# Ethernet_Shield.net
KiCad netlist of a schematic drawn in EAGLE
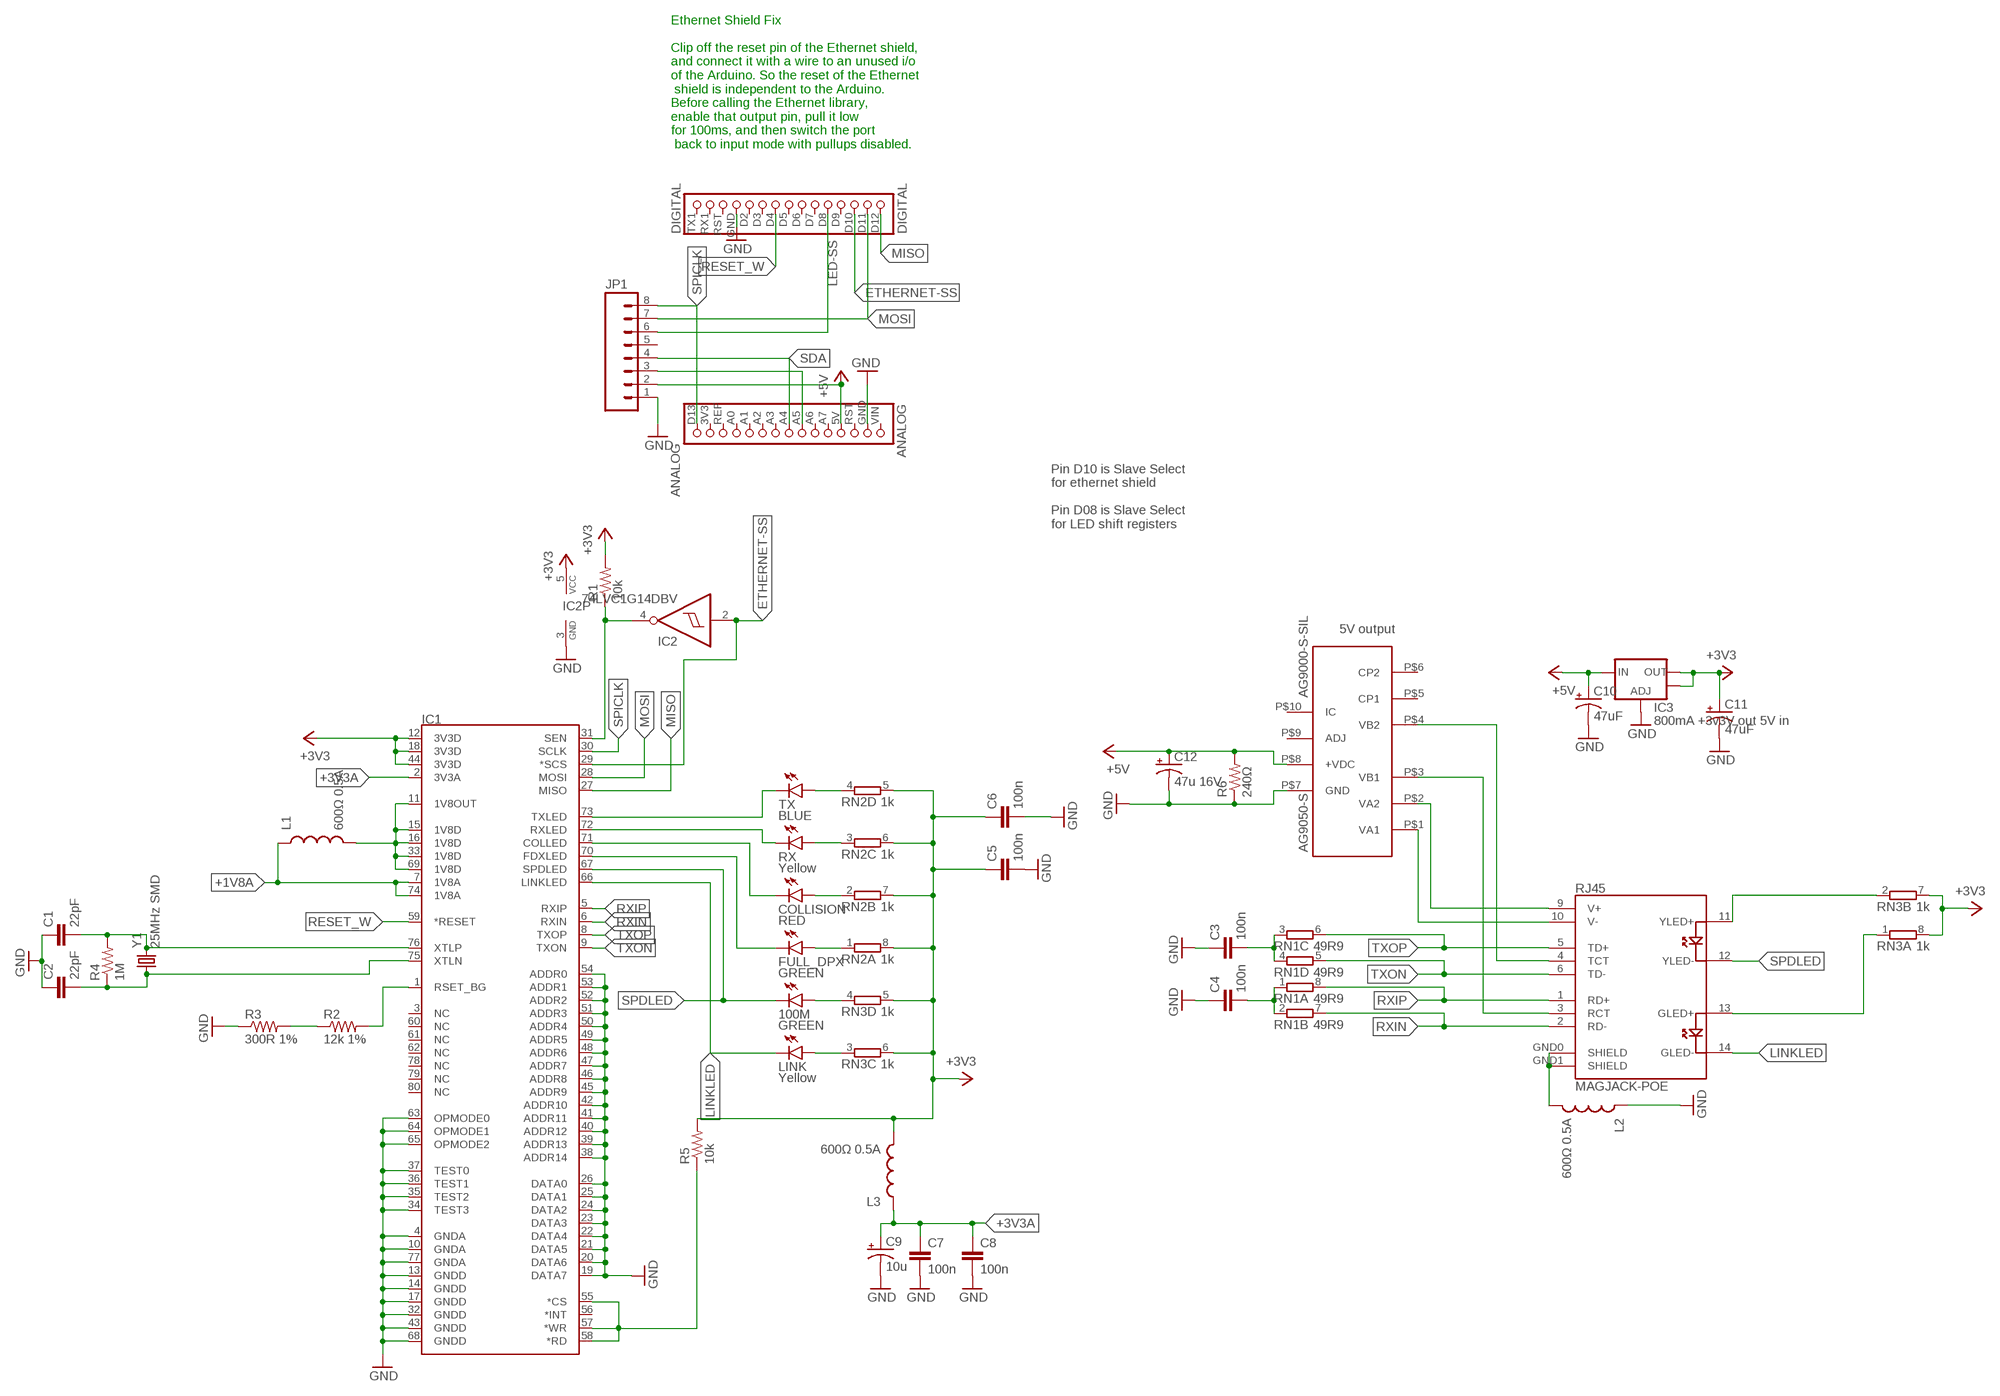
[diagram p0: schematic, sheet 1]

(export (version "E")
  (design (tool "Eeschema 10.0.6"))
  (components
    (comp (ref "100M")
      (value "GREEN")
      (footprint "eagle-import:LED-0603")
      (libsource (lib "eagle-import") (part "LED-GREEN0603"))
    )
    (comp (ref "AG9050-S")
      (value "AG9000-S-SIL")
      (footprint "eagle-import:AG9000-S")
      (libsource (lib "eagle-import") (part "AG9000-S-SIL"))
    )
    (comp (ref "ANALOG")
      (value "ANALOG")
      (footprint "eagle-import:A1X15")
      (libsource (lib "eagle-import") (part "ANALOG"))
    )
    (comp (ref "C1")
      (value "22pF")
      (footprint "eagle-import:0603-CAP")
      (libsource (lib "eagle-import") (part "22PF-50V-5%(0603)"))
    )
    (comp (ref "C2")
      (value "22pF")
      (footprint "eagle-import:0603-CAP")
      (libsource (lib "eagle-import") (part "22PF-50V-5%(0603)"))
    )
    (comp (ref "C3")
      (value "100n")
      (footprint "eagle-import:0402-CAP")
      (libsource (lib "eagle-import") (part "CAP0402-CAP"))
    )
    (comp (ref "C4")
      (value "100n")
      (footprint "eagle-import:0402-CAP")
      (libsource (lib "eagle-import") (part "CAP0402-CAP"))
    )
    (comp (ref "C5")
      (value "100n")
      (footprint "eagle-import:0402-CAP")
      (libsource (lib "eagle-import") (part "CAP0402-CAP"))
    )
    (comp (ref "C6")
      (value "100n")
      (footprint "eagle-import:0402-CAP")
      (libsource (lib "eagle-import") (part "CAP0402-CAP"))
    )
    (comp (ref "C7")
      (value "100n")
      (footprint "eagle-import:0402-CAP")
      (libsource (lib "eagle-import") (part "CAP0402-CAP"))
    )
    (comp (ref "C8")
      (value "100n")
      (footprint "eagle-import:0402-CAP")
      (libsource (lib "eagle-import") (part "CAP0402-CAP"))
    )
    (comp (ref "C9")
      (value "10u")
      (footprint "eagle-import:EIA3216")
      (libsource (lib "eagle-import") (part "CAP_POL1206"))
    )
    (comp (ref "C10")
      (value "47uF")
      (footprint "eagle-import:EIA3528")
      (libsource (lib "eagle-import") (part "47UF-10V-10%(TANT)"))
    )
    (comp (ref "C11")
      (value "47uF")
      (footprint "eagle-import:EIA3528")
      (libsource (lib "eagle-import") (part "47UF-10V-10%(TANT)"))
    )
    (comp (ref "C12")
      (value "47u 16V")
      (footprint "eagle-import:EIA3216")
      (libsource (lib "eagle-import") (part "CAP_POL1206"))
    )
    (comp (ref "COLLISION")
      (value "RED")
      (footprint "eagle-import:LED-0603")
      (libsource (lib "eagle-import") (part "LED-RED0603"))
    )
    (comp (ref "DIGITAL")
      (value "DIGITAL")
      (footprint "eagle-import:1X15")
      (libsource (lib "eagle-import") (part "DIGITALDIGITAL''"))
    )
    (comp (ref "FULL_DPX")
      (value "GREEN")
      (footprint "eagle-import:LED-0603")
      (libsource (lib "eagle-import") (part "LED-GREEN0603"))
    )
    (comp (ref "IC1")
      (value "W5100")
      (footprint "eagle-import:LQFP-80")
      (libsource (lib "eagle-import") (part "W5100"))
    )
    (comp (ref "IC2")
      (value "74LVC1G14DBV")
      (footprint "eagle-import:SOT23-5")
      (libsource (lib "eagle-import") (part "741G14DBVLVC"))
    )
    (comp (ref "IC3")
      (value "800mA +3v3V out 5V in")
      (footprint "eagle-import:SOT223")
      (libsource (lib "eagle-import") (part "V_REG_LM1117SOT223"))
    )
    (comp (ref "JP1")
      (value "M08")
      (footprint "eagle-import:1X08_ROUND")
      (libsource (lib "eagle-import") (part "M08"))
    )
    (comp (ref "L1")
      (value "600Ω 0.5A")
      (footprint "eagle-import:0805")
      (libsource (lib "eagle-import") (part "INDUCTOR0805"))
    )
    (comp (ref "L2")
      (value "600Ω 0.5A")
      (footprint "eagle-import:0805")
      (libsource (lib "eagle-import") (part "INDUCTOR0805"))
    )
    (comp (ref "L3")
      (value "600Ω 0.5A")
      (footprint "eagle-import:0805")
      (libsource (lib "eagle-import") (part "INDUCTOR0805"))
    )
    (comp (ref "LINK")
      (value "Yellow")
      (footprint "eagle-import:LED-0603")
      (libsource (lib "eagle-import") (part "LED-YELLOW0603"))
    )
    (comp (ref "R1")
      (value "10k")
      (footprint "eagle-import:0402-RES")
      (libsource (lib "eagle-import") (part "RESISTOR0402-RES"))
    )
    (comp (ref "R2")
      (value "12k 1%")
      (footprint "eagle-import:0402-RES")
      (libsource (lib "eagle-import") (part "RESISTOR0402-RES"))
    )
    (comp (ref "R3")
      (value "300R 1%")
      (footprint "eagle-import:0402-RES")
      (libsource (lib "eagle-import") (part "RESISTOR0402-RES"))
    )
    (comp (ref "R4")
      (value "1M")
      (footprint "eagle-import:0402-RES")
      (libsource (lib "eagle-import") (part "RESISTOR0402-RES"))
    )
    (comp (ref "R5")
      (value "10k")
      (footprint "eagle-import:0402-RES")
      (libsource (lib "eagle-import") (part "RESISTOR0402-RES"))
    )
    (comp (ref "R6")
      (value "240Ω")
      (footprint "eagle-import:0402-RES")
      (libsource (lib "eagle-import") (part "RESISTOR0402-RES"))
    )
    (comp (ref "RJ45")
      (value "MAGJACK-POE")
      (footprint "eagle-import:MAGJACK-POE")
      (libsource (lib "eagle-import") (part "MAGJACK-POE"))
    )
    (comp (ref "RN1")
      (value "49R9")
      (footprint "eagle-import:CAY16")
      (libsource (lib "eagle-import") (part "4R-NCAY16"))
    )
    (comp (ref "RN2")
      (value "1k")
      (footprint "eagle-import:CAY16")
      (libsource (lib "eagle-import") (part "4R-NCAY16"))
    )
    (comp (ref "RN3")
      (value "1k")
      (footprint "eagle-import:CAY16")
      (libsource (lib "eagle-import") (part "4R-NCAY16"))
    )
    (comp (ref "RX")
      (value "Yellow")
      (footprint "eagle-import:LED-0603")
      (libsource (lib "eagle-import") (part "LED-YELLOW0603"))
    )
    (comp (ref "TX")
      (value "BLUE")
      (footprint "eagle-import:LED-0603")
      (libsource (lib "eagle-import") (part "LED-BLUE0603"))
    )
    (comp (ref "Y1")
      (value "25MHz SMD")
      (footprint "eagle-import:HC49UP")
      (libsource (lib "eagle-import") (part "CRYSTALSMD"))
    )
  )
  (nets
    (net (code "1") (name "+1V8A") (class "Default")
      (node (ref "IC1") (pin "7") (pinfunction "1V8A_7") (pintype "bidirectional"))
      (node (ref "IC1") (pin "74") (pinfunction "1V8A_74") (pintype "bidirectional"))
      (node (ref "L1") (pin "1") (pinfunction "1_1") (pintype "passive"))
    )
    (net (code "2") (name "+3V3") (class "Default")
      (node (ref "C11") (pin "A") (pinfunction "+_A") (pintype "passive"))
      (node (ref "C5") (pin "1") (pinfunction "1_1") (pintype "passive"))
      (node (ref "C6") (pin "1") (pinfunction "1_1") (pintype "passive"))
      (node (ref "IC1") (pin "12") (pinfunction "3V3D_12") (pintype "bidirectional"))
      (node (ref "IC1") (pin "18") (pinfunction "3V3D_18") (pintype "bidirectional"))
      (node (ref "IC1") (pin "44") (pinfunction "3V3D_44") (pintype "bidirectional"))
      (node (ref "IC2") (pin "5") (pinfunction "VCC_5") (pintype "power_in"))
      (node (ref "IC3") (pin "2") (pinfunction "OUT_2") (pintype "output"))
      (node (ref "IC3") (pin "4") (pinfunction "OUT_4") (pintype "output"))
      (node (ref "L3") (pin "2") (pinfunction "2_2") (pintype "passive"))
      (node (ref "R1") (pin "2") (pinfunction "2_2") (pintype "passive"))
      (node (ref "R5") (pin "2") (pinfunction "2_2") (pintype "passive"))
      (node (ref "RN2") (pin "5") (pinfunction "2_5") (pintype "passive"))
      (node (ref "RN2") (pin "6") (pinfunction "2_6") (pintype "passive"))
      (node (ref "RN2") (pin "7") (pinfunction "2_7") (pintype "passive"))
      (node (ref "RN2") (pin "8") (pinfunction "2_8") (pintype "passive"))
      (node (ref "RN3") (pin "5") (pinfunction "2_5") (pintype "passive"))
      (node (ref "RN3") (pin "6") (pinfunction "2_6") (pintype "passive"))
      (node (ref "RN3") (pin "7") (pinfunction "2_7") (pintype "passive"))
      (node (ref "RN3") (pin "8") (pinfunction "2_8") (pintype "passive"))
    )
    (net (code "3") (name "+3V3A") (class "Default")
      (node (ref "C7") (pin "1") (pinfunction "1_1") (pintype "passive"))
      (node (ref "C8") (pin "1") (pinfunction "1_1") (pintype "passive"))
      (node (ref "C9") (pin "A") (pinfunction "+_A") (pintype "passive"))
      (node (ref "IC1") (pin "2") (pinfunction "3V3A_2") (pintype "bidirectional"))
      (node (ref "L3") (pin "1") (pinfunction "1_1") (pintype "passive"))
    )
    (net (code "4") (name "+5V") (class "Default")
      (node (ref "AG9050-S") (pin "P$8") (pinfunction "+VDC_P$8") (pintype "output"))
      (node (ref "ANALOG") (pin "5V") (pinfunction "5V_5V") (pintype "passive"))
      (node (ref "C10") (pin "A") (pinfunction "+_A") (pintype "passive"))
      (node (ref "C12") (pin "A") (pinfunction "+_A") (pintype "passive"))
      (node (ref "IC3") (pin "3") (pinfunction "IN_3") (pintype "input"))
      (node (ref "JP1") (pin "2") (pinfunction "2_2") (pintype "passive"))
      (node (ref "R6") (pin "2") (pinfunction "2_2") (pintype "passive"))
    )
    (net (code "5") (name "/LED-SS") (class "Default")
      (node (ref "DIGITAL") (pin "D8") (pinfunction "D8_D8") (pintype "passive"))
      (node (ref "JP1") (pin "6") (pinfunction "6_6") (pintype "passive"))
    )
    (net (code "6") (name "ETHERNET-SS") (class "Default")
      (node (ref "DIGITAL") (pin "D10") (pinfunction "D10_D10") (pintype "passive"))
      (node (ref "IC1") (pin "29") (pinfunction "*SCS_29") (pintype "bidirectional"))
      (node (ref "IC2") (pin "2") (pinfunction "I_2") (pintype "input"))
    )
    (net (code "7") (name "GND") (class "Default")
      (node (ref "AG9050-S") (pin "P$7") (pinfunction "GND_P$7") (pintype "bidirectional"))
      (node (ref "ANALOG") (pin "GND") (pinfunction "GND_GND") (pintype "passive"))
      (node (ref "C1") (pin "1") (pinfunction "1_1") (pintype "passive"))
      (node (ref "C10") (pin "C") (pinfunction "-_C") (pintype "passive"))
      (node (ref "C11") (pin "C") (pinfunction "-_C") (pintype "passive"))
      (node (ref "C12") (pin "C") (pinfunction "-_C") (pintype "passive"))
      (node (ref "C2") (pin "1") (pinfunction "1_1") (pintype "passive"))
      (node (ref "C3") (pin "1") (pinfunction "1_1") (pintype "passive"))
      (node (ref "C4") (pin "1") (pinfunction "1_1") (pintype "passive"))
      (node (ref "C5") (pin "2") (pinfunction "2_2") (pintype "passive"))
      (node (ref "C6") (pin "2") (pinfunction "2_2") (pintype "passive"))
      (node (ref "C7") (pin "2") (pinfunction "2_2") (pintype "passive"))
      (node (ref "C8") (pin "2") (pinfunction "2_2") (pintype "passive"))
      (node (ref "C9") (pin "C") (pinfunction "-_C") (pintype "passive"))
      (node (ref "DIGITAL") (pin "GND") (pinfunction "GND_GND") (pintype "passive"))
      (node (ref "IC1") (pin "10") (pinfunction "GNDA_10") (pintype "bidirectional"))
      (node (ref "IC1") (pin "13") (pinfunction "GNDD_13") (pintype "bidirectional"))
      (node (ref "IC1") (pin "14") (pinfunction "GNDD_14") (pintype "bidirectional"))
      (node (ref "IC1") (pin "17") (pinfunction "GNDD_17") (pintype "bidirectional"))
      (node (ref "IC1") (pin "19") (pinfunction "DATA7_19") (pintype "bidirectional"))
      (node (ref "IC1") (pin "20") (pinfunction "DATA6_20") (pintype "bidirectional"))
      (node (ref "IC1") (pin "21") (pinfunction "DATA5_21") (pintype "bidirectional"))
      (node (ref "IC1") (pin "22") (pinfunction "DATA4_22") (pintype "bidirectional"))
      (node (ref "IC1") (pin "23") (pinfunction "DATA3_23") (pintype "bidirectional"))
      (node (ref "IC1") (pin "24") (pinfunction "DATA2_24") (pintype "bidirectional"))
      (node (ref "IC1") (pin "25") (pinfunction "DATA1_25") (pintype "bidirectional"))
      (node (ref "IC1") (pin "26") (pinfunction "DATA0_26") (pintype "bidirectional"))
      (node (ref "IC1") (pin "32") (pinfunction "GNDD_32") (pintype "bidirectional"))
      (node (ref "IC1") (pin "34") (pinfunction "TEST3_34") (pintype "bidirectional"))
      (node (ref "IC1") (pin "35") (pinfunction "TEST2_35") (pintype "bidirectional"))
      (node (ref "IC1") (pin "36") (pinfunction "TEST1_36") (pintype "bidirectional"))
      (node (ref "IC1") (pin "37") (pinfunction "TEST0_37") (pintype "bidirectional"))
      (node (ref "IC1") (pin "38") (pinfunction "ADDR14_38") (pintype "bidirectional"))
      (node (ref "IC1") (pin "39") (pinfunction "ADDR13_39") (pintype "bidirectional"))
      (node (ref "IC1") (pin "4") (pinfunction "GNDA_4") (pintype "bidirectional"))
      (node (ref "IC1") (pin "40") (pinfunction "ADDR12_40") (pintype "bidirectional"))
      (node (ref "IC1") (pin "41") (pinfunction "ADDR11_41") (pintype "bidirectional"))
      (node (ref "IC1") (pin "42") (pinfunction "ADDR10_42") (pintype "bidirectional"))
      (node (ref "IC1") (pin "43") (pinfunction "GNDD_43") (pintype "bidirectional"))
      (node (ref "IC1") (pin "45") (pinfunction "ADDR9_45") (pintype "bidirectional"))
      (node (ref "IC1") (pin "46") (pinfunction "ADDR8_46") (pintype "bidirectional"))
      (node (ref "IC1") (pin "47") (pinfunction "ADDR7_47") (pintype "bidirectional"))
      (node (ref "IC1") (pin "48") (pinfunction "ADDR6_48") (pintype "bidirectional"))
      (node (ref "IC1") (pin "49") (pinfunction "ADDR5_49") (pintype "bidirectional"))
      (node (ref "IC1") (pin "50") (pinfunction "ADDR4_50") (pintype "bidirectional"))
      (node (ref "IC1") (pin "51") (pinfunction "ADDR3_51") (pintype "bidirectional"))
      (node (ref "IC1") (pin "52") (pinfunction "ADDR2_52") (pintype "bidirectional"))
      (node (ref "IC1") (pin "53") (pinfunction "ADDR1_53") (pintype "bidirectional"))
      (node (ref "IC1") (pin "54") (pinfunction "ADDR0_54") (pintype "bidirectional"))
      (node (ref "IC1") (pin "63") (pinfunction "OPMODE0_63") (pintype "bidirectional"))
      (node (ref "IC1") (pin "64") (pinfunction "OPMODE1_64") (pintype "bidirectional"))
      (node (ref "IC1") (pin "65") (pinfunction "OPMODE2_65") (pintype "bidirectional"))
      (node (ref "IC1") (pin "68") (pinfunction "GNDD_68") (pintype "bidirectional"))
      (node (ref "IC1") (pin "77") (pinfunction "GNDA_77") (pintype "bidirectional"))
      (node (ref "IC2") (pin "3") (pinfunction "GND_3") (pintype "power_in"))
      (node (ref "IC3") (pin "1") (pinfunction "ADJ_1") (pintype "input"))
      (node (ref "JP1") (pin "1") (pinfunction "1_1") (pintype "passive"))
      (node (ref "L2") (pin "1") (pinfunction "1_1") (pintype "passive"))
      (node (ref "R3") (pin "1") (pinfunction "1_1") (pintype "passive"))
      (node (ref "R6") (pin "1") (pinfunction "1_1") (pintype "passive"))
    )
    (net (code "8") (name "LINKLED") (class "Default")
      (node (ref "IC1") (pin "66") (pinfunction "LINKLED_66") (pintype "bidirectional"))
      (node (ref "LINK") (pin "C") (pinfunction "C_C") (pintype "passive"))
      (node (ref "RJ45") (pin "14") (pinfunction "GLED-_14") (pintype "bidirectional"))
    )
    (net (code "9") (name "MISO") (class "Default")
      (node (ref "DIGITAL") (pin "D12") (pinfunction "D12_D12") (pintype "passive"))
      (node (ref "IC1") (pin "27") (pinfunction "MISO_27") (pintype "bidirectional"))
    )
    (net (code "10") (name "MOSI") (class "Default")
      (node (ref "DIGITAL") (pin "D11") (pinfunction "D11_D11") (pintype "passive"))
      (node (ref "IC1") (pin "28") (pinfunction "MOSI_28") (pintype "bidirectional"))
      (node (ref "JP1") (pin "7") (pinfunction "7_7") (pintype "passive"))
    )
    (net (code "11") (name "Net-(AG9050-S-VA1)") (class "Default")
      (node (ref "AG9050-S") (pin "P$1") (pinfunction "VA1_P$1") (pintype "input"))
      (node (ref "RJ45") (pin "10") (pinfunction "V-_10") (pintype "bidirectional"))
    )
    (net (code "12") (name "Net-(AG9050-S-VA2)") (class "Default")
      (node (ref "AG9050-S") (pin "P$2") (pinfunction "VA2_P$2") (pintype "input"))
      (node (ref "RJ45") (pin "9") (pinfunction "V+_9") (pintype "bidirectional"))
    )
    (net (code "13") (name "Net-(AG9050-S-VB1)") (class "Default")
      (node (ref "AG9050-S") (pin "P$3") (pinfunction "VB1_P$3") (pintype "input"))
      (node (ref "RJ45") (pin "3") (pinfunction "RCT_3") (pintype "bidirectional"))
    )
    (net (code "14") (name "Net-(AG9050-S-VB2)") (class "Default")
      (node (ref "AG9050-S") (pin "P$4") (pinfunction "VB2_P$4") (pintype "input"))
      (node (ref "RJ45") (pin "4") (pinfunction "TCT_4") (pintype "bidirectional"))
    )
    (net (code "15") (name "Net-(ANALOG-PadA5)") (class "Default")
      (node (ref "ANALOG") (pin "A5") (pinfunction "A5_A5") (pintype "passive"))
      (node (ref "JP1") (pin "3") (pinfunction "3_3") (pintype "passive"))
    )
    (net (code "16") (name "Net-(FULL_DPX-PadA)") (class "Default")
      (node (ref "FULL_DPX") (pin "A") (pinfunction "A_A") (pintype "passive"))
      (node (ref "RN2") (pin "1") (pinfunction "1_1") (pintype "passive"))
    )
    (net (code "17") (name "Net-(IC1-*CS)") (class "Default")
      (node (ref "IC1") (pin "55") (pinfunction "*CS_55") (pintype "bidirectional"))
      (node (ref "IC1") (pin "57") (pinfunction "*WR_57") (pintype "bidirectional"))
      (node (ref "IC1") (pin "58") (pinfunction "*RD_58") (pintype "bidirectional"))
      (node (ref "R5") (pin "1") (pinfunction "1_1") (pintype "passive"))
    )
    (net (code "18") (name "Net-(IC1-1V8OUT)") (class "Default")
      (node (ref "IC1") (pin "11") (pinfunction "1V8OUT_11") (pintype "bidirectional"))
      (node (ref "IC1") (pin "15") (pinfunction "1V8D_15") (pintype "bidirectional"))
      (node (ref "IC1") (pin "16") (pinfunction "1V8D_16") (pintype "bidirectional"))
      (node (ref "IC1") (pin "33") (pinfunction "1V8D_33") (pintype "bidirectional"))
      (node (ref "IC1") (pin "69") (pinfunction "1V8D_69") (pintype "bidirectional"))
      (node (ref "L1") (pin "2") (pinfunction "2_2") (pintype "passive"))
    )
    (net (code "19") (name "Net-(IC1-COLLED)") (class "Default")
      (node (ref "COLLISION") (pin "C") (pinfunction "C_C") (pintype "passive"))
      (node (ref "IC1") (pin "71") (pinfunction "COLLED_71") (pintype "bidirectional"))
    )
    (net (code "20") (name "Net-(IC1-FDXLED)") (class "Default")
      (node (ref "FULL_DPX") (pin "C") (pinfunction "C_C") (pintype "passive"))
      (node (ref "IC1") (pin "70") (pinfunction "FDXLED_70") (pintype "bidirectional"))
    )
    (net (code "21") (name "Net-(IC1-RSET_BG)") (class "Default")
      (node (ref "IC1") (pin "1") (pinfunction "RSET_BG_1") (pintype "bidirectional"))
      (node (ref "R2") (pin "2") (pinfunction "2_2") (pintype "passive"))
    )
    (net (code "22") (name "Net-(IC1-RXLED)") (class "Default")
      (node (ref "IC1") (pin "72") (pinfunction "RXLED_72") (pintype "bidirectional"))
      (node (ref "RX") (pin "C") (pinfunction "C_C") (pintype "passive"))
    )
    (net (code "23") (name "Net-(IC1-SEN)") (class "Default")
      (node (ref "IC1") (pin "31") (pinfunction "SEN_31") (pintype "bidirectional"))
      (node (ref "IC2") (pin "4") (pinfunction "O_4") (pintype "output"))
      (node (ref "R1") (pin "1") (pinfunction "1_1") (pintype "passive"))
    )
    (net (code "24") (name "Net-(IC1-TXLED)") (class "Default")
      (node (ref "IC1") (pin "73") (pinfunction "TXLED_73") (pintype "bidirectional"))
      (node (ref "TX") (pin "C") (pinfunction "C_C") (pintype "passive"))
    )
    (net (code "25") (name "Net-(IC1-XTLN)") (class "Default")
      (node (ref "C2") (pin "2") (pinfunction "2_2") (pintype "passive"))
      (node (ref "IC1") (pin "75") (pinfunction "XTLN_75") (pintype "bidirectional"))
      (node (ref "R4") (pin "1") (pinfunction "1_1") (pintype "passive"))
      (node (ref "Y1") (pin "1") (pinfunction "1_1") (pintype "passive"))
    )
    (net (code "26") (name "Net-(IC1-XTLP)") (class "Default")
      (node (ref "C1") (pin "2") (pinfunction "2_2") (pintype "passive"))
      (node (ref "IC1") (pin "76") (pinfunction "XTLP_76") (pintype "bidirectional"))
      (node (ref "R4") (pin "2") (pinfunction "2_2") (pintype "passive"))
      (node (ref "Y1") (pin "2") (pinfunction "2_2") (pintype "passive"))
    )
    (net (code "27") (name "Net-(L2-Pad2)") (class "Default")
      (node (ref "L2") (pin "2") (pinfunction "2_2") (pintype "passive"))
      (node (ref "RJ45") (pin "GND0") (pinfunction "SHIELD_GND0") (pintype "bidirectional"))
      (node (ref "RJ45") (pin "GND1") (pinfunction "SHIELD_GND1") (pintype "bidirectional"))
    )
    (net (code "28") (name "Net-(R2-Pad1)") (class "Default")
      (node (ref "R2") (pin "1") (pinfunction "1_1") (pintype "passive"))
      (node (ref "R3") (pin "2") (pinfunction "2_2") (pintype "passive"))
    )
    (net (code "29") (name "Net-(RJ45-GLED+)") (class "Default")
      (node (ref "RJ45") (pin "13") (pinfunction "GLED+_13") (pintype "bidirectional"))
      (node (ref "RN3") (pin "1") (pinfunction "1_1") (pintype "passive"))
    )
    (net (code "30") (name "Net-(RJ45-YLED+)") (class "Default")
      (node (ref "RJ45") (pin "11") (pinfunction "YLED+_11") (pintype "bidirectional"))
      (node (ref "RN3") (pin "2") (pinfunction "1_2") (pintype "passive"))
    )
    (net (code "31") (name "Net-(RN1B-1)") (class "Default")
      (node (ref "C4") (pin "2") (pinfunction "2_2") (pintype "passive"))
      (node (ref "RN1") (pin "1") (pinfunction "1_1") (pintype "passive"))
      (node (ref "RN1") (pin "2") (pinfunction "1_2") (pintype "passive"))
    )
    (net (code "32") (name "Net-(RN1C-1)") (class "Default")
      (node (ref "C3") (pin "2") (pinfunction "2_2") (pintype "passive"))
      (node (ref "RN1") (pin "3") (pinfunction "1_3") (pintype "passive"))
      (node (ref "RN1") (pin "4") (pinfunction "1_4") (pintype "passive"))
    )
    (net (code "33") (name "Net-(RN2B-1)") (class "Default")
      (node (ref "COLLISION") (pin "A") (pinfunction "A_A") (pintype "passive"))
      (node (ref "RN2") (pin "2") (pinfunction "1_2") (pintype "passive"))
    )
    (net (code "34") (name "Net-(RN2C-1)") (class "Default")
      (node (ref "RN2") (pin "3") (pinfunction "1_3") (pintype "passive"))
      (node (ref "RX") (pin "A") (pinfunction "A_A") (pintype "passive"))
    )
    (net (code "35") (name "Net-(RN2D-1)") (class "Default")
      (node (ref "RN2") (pin "4") (pinfunction "1_4") (pintype "passive"))
      (node (ref "TX") (pin "A") (pinfunction "A_A") (pintype "passive"))
    )
    (net (code "36") (name "Net-(RN3C-1)") (class "Default")
      (node (ref "LINK") (pin "A") (pinfunction "A_A") (pintype "passive"))
      (node (ref "RN3") (pin "3") (pinfunction "1_3") (pintype "passive"))
    )
    (net (code "37") (name "Net-(RN3D-1)") (class "Default")
      (node (ref "100M") (pin "A") (pinfunction "A_A") (pintype "passive"))
      (node (ref "RN3") (pin "4") (pinfunction "1_4") (pintype "passive"))
    )
    (net (code "38") (name "RESET_W") (class "Default")
      (node (ref "DIGITAL") (pin "D4") (pinfunction "D4_D4") (pintype "passive"))
      (node (ref "IC1") (pin "59") (pinfunction "*RESET_59") (pintype "bidirectional"))
    )
    (net (code "39") (name "RXIN") (class "Default")
      (node (ref "IC1") (pin "6") (pinfunction "RXIN_6") (pintype "bidirectional"))
      (node (ref "RJ45") (pin "2") (pinfunction "RD-_2") (pintype "bidirectional"))
      (node (ref "RN1") (pin "7") (pinfunction "2_7") (pintype "passive"))
    )
    (net (code "40") (name "RXIP") (class "Default")
      (node (ref "IC1") (pin "5") (pinfunction "RXIP_5") (pintype "bidirectional"))
      (node (ref "RJ45") (pin "1") (pinfunction "RD+_1") (pintype "bidirectional"))
      (node (ref "RN1") (pin "8") (pinfunction "2_8") (pintype "passive"))
    )
    (net (code "41") (name "SDA") (class "Default")
      (node (ref "ANALOG") (pin "A4") (pinfunction "A4_A4") (pintype "passive"))
      (node (ref "JP1") (pin "4") (pinfunction "4_4") (pintype "passive"))
    )
    (net (code "42") (name "SPDLED") (class "Default")
      (node (ref "100M") (pin "C") (pinfunction "C_C") (pintype "passive"))
      (node (ref "IC1") (pin "67") (pinfunction "SPDLED_67") (pintype "bidirectional"))
      (node (ref "RJ45") (pin "12") (pinfunction "YLED-_12") (pintype "bidirectional"))
    )
    (net (code "43") (name "SPICLK") (class "Default")
      (node (ref "ANALOG") (pin "D13") (pinfunction "D13_D13") (pintype "passive"))
      (node (ref "IC1") (pin "30") (pinfunction "SCLK_30") (pintype "bidirectional"))
      (node (ref "JP1") (pin "8") (pinfunction "8_8") (pintype "passive"))
    )
    (net (code "44") (name "TXON") (class "Default")
      (node (ref "IC1") (pin "9") (pinfunction "TXON_9") (pintype "bidirectional"))
      (node (ref "RJ45") (pin "6") (pinfunction "TD-_6") (pintype "bidirectional"))
      (node (ref "RN1") (pin "5") (pinfunction "2_5") (pintype "passive"))
    )
    (net (code "45") (name "TXOP") (class "Default")
      (node (ref "IC1") (pin "8") (pinfunction "TXOP_8") (pintype "bidirectional"))
      (node (ref "RJ45") (pin "5") (pinfunction "TD+_5") (pintype "bidirectional"))
      (node (ref "RN1") (pin "6") (pinfunction "2_6") (pintype "passive"))
    )
    (net (code "46") (name "unconnected-(AG9050-S-ADJ-PadP$9)") (class "Default")
      (node (ref "AG9050-S") (pin "P$9") (pinfunction "ADJ_P$9") (pintype "bidirectional"))
    )
    (net (code "47") (name "unconnected-(AG9050-S-CP1-PadP$5)") (class "Default")
      (node (ref "AG9050-S") (pin "P$5") (pinfunction "CP1_P$5") (pintype "passive"))
    )
    (net (code "48") (name "unconnected-(AG9050-S-CP2-PadP$6)") (class "Default")
      (node (ref "AG9050-S") (pin "P$6") (pinfunction "CP2_P$6") (pintype "passive"))
    )
    (net (code "49") (name "unconnected-(AG9050-S-IC-PadP$10)") (class "Default")
      (node (ref "AG9050-S") (pin "P$10") (pinfunction "IC_P$10") (pintype "no_connect"))
    )
    (net (code "50") (name "unconnected-(ANALOG-Pad3V3)") (class "Default")
      (node (ref "ANALOG") (pin "3V3") (pinfunction "3V3_3V3") (pintype "passive"))
    )
    (net (code "51") (name "unconnected-(ANALOG-PadA0)") (class "Default")
      (node (ref "ANALOG") (pin "A0") (pinfunction "A0_A0") (pintype "passive"))
    )
    (net (code "52") (name "unconnected-(ANALOG-PadA1)") (class "Default")
      (node (ref "ANALOG") (pin "A1") (pinfunction "A1_A1") (pintype "passive"))
    )
    (net (code "53") (name "unconnected-(ANALOG-PadA2)") (class "Default")
      (node (ref "ANALOG") (pin "A2") (pinfunction "A2_A2") (pintype "passive"))
    )
    (net (code "54") (name "unconnected-(ANALOG-PadA3)") (class "Default")
      (node (ref "ANALOG") (pin "A3") (pinfunction "A3_A3") (pintype "passive"))
    )
    (net (code "55") (name "unconnected-(ANALOG-PadA6)") (class "Default")
      (node (ref "ANALOG") (pin "A6") (pinfunction "A6_A6") (pintype "passive"))
    )
    (net (code "56") (name "unconnected-(ANALOG-PadA7)") (class "Default")
      (node (ref "ANALOG") (pin "A7") (pinfunction "A7_A7") (pintype "passive"))
    )
    (net (code "57") (name "unconnected-(ANALOG-PadREF)") (class "Default")
      (node (ref "ANALOG") (pin "REF") (pinfunction "REF_REF") (pintype "passive"))
    )
    (net (code "58") (name "unconnected-(ANALOG-PadRST)") (class "Default")
      (node (ref "ANALOG") (pin "RST") (pinfunction "RST_RST") (pintype "passive"))
    )
    (net (code "59") (name "unconnected-(ANALOG-PadVIN)") (class "Default")
      (node (ref "ANALOG") (pin "VIN") (pinfunction "VIN_VIN") (pintype "passive"))
    )
    (net (code "60") (name "unconnected-(DIGITAL-PadD2)") (class "Default")
      (node (ref "DIGITAL") (pin "D2") (pinfunction "D2_D2") (pintype "passive"))
    )
    (net (code "61") (name "unconnected-(DIGITAL-PadD3)") (class "Default")
      (node (ref "DIGITAL") (pin "D3") (pinfunction "D3_D3") (pintype "passive"))
    )
    (net (code "62") (name "unconnected-(DIGITAL-PadD5)") (class "Default")
      (node (ref "DIGITAL") (pin "D5") (pinfunction "D5_D5") (pintype "passive"))
    )
    (net (code "63") (name "unconnected-(DIGITAL-PadD6)") (class "Default")
      (node (ref "DIGITAL") (pin "D6") (pinfunction "D6_D6") (pintype "passive"))
    )
    (net (code "64") (name "unconnected-(DIGITAL-PadD7)") (class "Default")
      (node (ref "DIGITAL") (pin "D7") (pinfunction "D7_D7") (pintype "passive"))
    )
    (net (code "65") (name "unconnected-(DIGITAL-PadD9)") (class "Default")
      (node (ref "DIGITAL") (pin "D9") (pinfunction "D9_D9") (pintype "passive"))
    )
    (net (code "66") (name "unconnected-(DIGITAL-PadRST)") (class "Default")
      (node (ref "DIGITAL") (pin "RST") (pinfunction "RST_RST") (pintype "passive"))
    )
    (net (code "67") (name "unconnected-(DIGITAL-PadRX1)") (class "Default")
      (node (ref "DIGITAL") (pin "RX1") (pinfunction "RX1_RX1") (pintype "passive"))
    )
    (net (code "68") (name "unconnected-(DIGITAL-PadTX1)") (class "Default")
      (node (ref "DIGITAL") (pin "TX1") (pinfunction "TX1_TX1") (pintype "passive"))
    )
    (net (code "69") (name "unconnected-(IC1-*INT-Pad56)") (class "Default")
      (node (ref "IC1") (pin "56") (pinfunction "*INT_56") (pintype "bidirectional"))
    )
    (net (code "70") (name "unconnected-(IC1-NC-Pad3)") (class "Default")
      (node (ref "IC1") (pin "3") (pinfunction "NC_3") (pintype "bidirectional"))
    )
    (net (code "71") (name "unconnected-(IC1-NC-Pad60)") (class "Default")
      (node (ref "IC1") (pin "60") (pinfunction "NC_60") (pintype "bidirectional"))
    )
    (net (code "72") (name "unconnected-(IC1-NC-Pad61)") (class "Default")
      (node (ref "IC1") (pin "61") (pinfunction "NC_61") (pintype "bidirectional"))
    )
    (net (code "73") (name "unconnected-(IC1-NC-Pad62)") (class "Default")
      (node (ref "IC1") (pin "62") (pinfunction "NC_62") (pintype "bidirectional"))
    )
    (net (code "74") (name "unconnected-(IC1-NC-Pad78)") (class "Default")
      (node (ref "IC1") (pin "78") (pinfunction "NC_78") (pintype "bidirectional"))
    )
    (net (code "75") (name "unconnected-(IC1-NC-Pad79)") (class "Default")
      (node (ref "IC1") (pin "79") (pinfunction "NC_79") (pintype "bidirectional"))
    )
    (net (code "76") (name "unconnected-(IC1-NC-Pad80)") (class "Default")
      (node (ref "IC1") (pin "80") (pinfunction "NC_80") (pintype "bidirectional"))
    )
    (net (code "77") (name "unconnected-(JP1-Pad5)") (class "Default")
      (node (ref "JP1") (pin "5") (pinfunction "5_5") (pintype "passive"))
    )
  )
)
